# BREAKOUT_SOC8.net
KiCad netlist of a schematic drawn in EAGLE
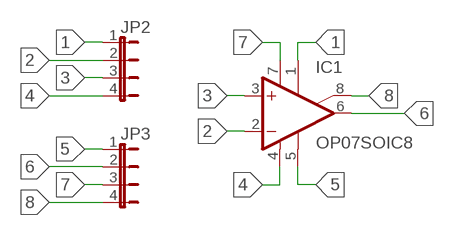
[diagram p0: schematic, sheet 1]

(export (version "E")
  (design (tool "Eeschema 10.0.6"))
  (components
    (comp (ref "IC1")
      (value "OP07SOIC8")
      (footprint "eagle-import:SOIC8")
      (libsource (lib "eagle-import") (part "OP07SOIC8"))
    )
    (comp (ref "JP2")
      (value "JP4E")
      (footprint "eagle-import:JP4")
      (libsource (lib "eagle-import") (part "JP4E"))
    )
    (comp (ref "JP3")
      (value "JP4E")
      (footprint "eagle-import:JP4")
      (libsource (lib "eagle-import") (part "JP4E"))
    )
  )
  (nets
    (net (code "1") (name "1") (class "Default")
      (node (ref "IC1") (pin "1") (pinfunction "ON1_1") (pintype "passive"))
      (node (ref "JP2") (pin "1") (pinfunction "1_1") (pintype "passive"))
    )
    (net (code "2") (name "2") (class "Default")
      (node (ref "IC1") (pin "2") (pinfunction "-IN_2") (pintype "input"))
      (node (ref "JP2") (pin "2") (pinfunction "2_2") (pintype "passive"))
    )
    (net (code "3") (name "3") (class "Default")
      (node (ref "IC1") (pin "3") (pinfunction "+IN_3") (pintype "input"))
      (node (ref "JP2") (pin "3") (pinfunction "3_3") (pintype "passive"))
    )
    (net (code "4") (name "4") (class "Default")
      (node (ref "IC1") (pin "4") (pinfunction "V-_4") (pintype "power_in"))
      (node (ref "JP2") (pin "4") (pinfunction "4_4") (pintype "passive"))
    )
    (net (code "5") (name "5") (class "Default")
      (node (ref "IC1") (pin "5") (pinfunction "OPT_5") (pintype "passive"))
      (node (ref "JP3") (pin "1") (pinfunction "1_1") (pintype "passive"))
    )
    (net (code "6") (name "6") (class "Default")
      (node (ref "IC1") (pin "6") (pinfunction "OUT_6") (pintype "output"))
      (node (ref "JP3") (pin "2") (pinfunction "2_2") (pintype "passive"))
    )
    (net (code "7") (name "7") (class "Default")
      (node (ref "IC1") (pin "7") (pinfunction "V+_7") (pintype "power_in"))
      (node (ref "JP3") (pin "3") (pinfunction "3_3") (pintype "passive"))
    )
    (net (code "8") (name "8") (class "Default")
      (node (ref "IC1") (pin "8") (pinfunction "ON2_8") (pintype "passive"))
      (node (ref "JP3") (pin "4") (pinfunction "4_4") (pintype "passive"))
    )
  )
)
